# SDCARD.net
KiCad netlist of a schematic drawn in Altium Designer
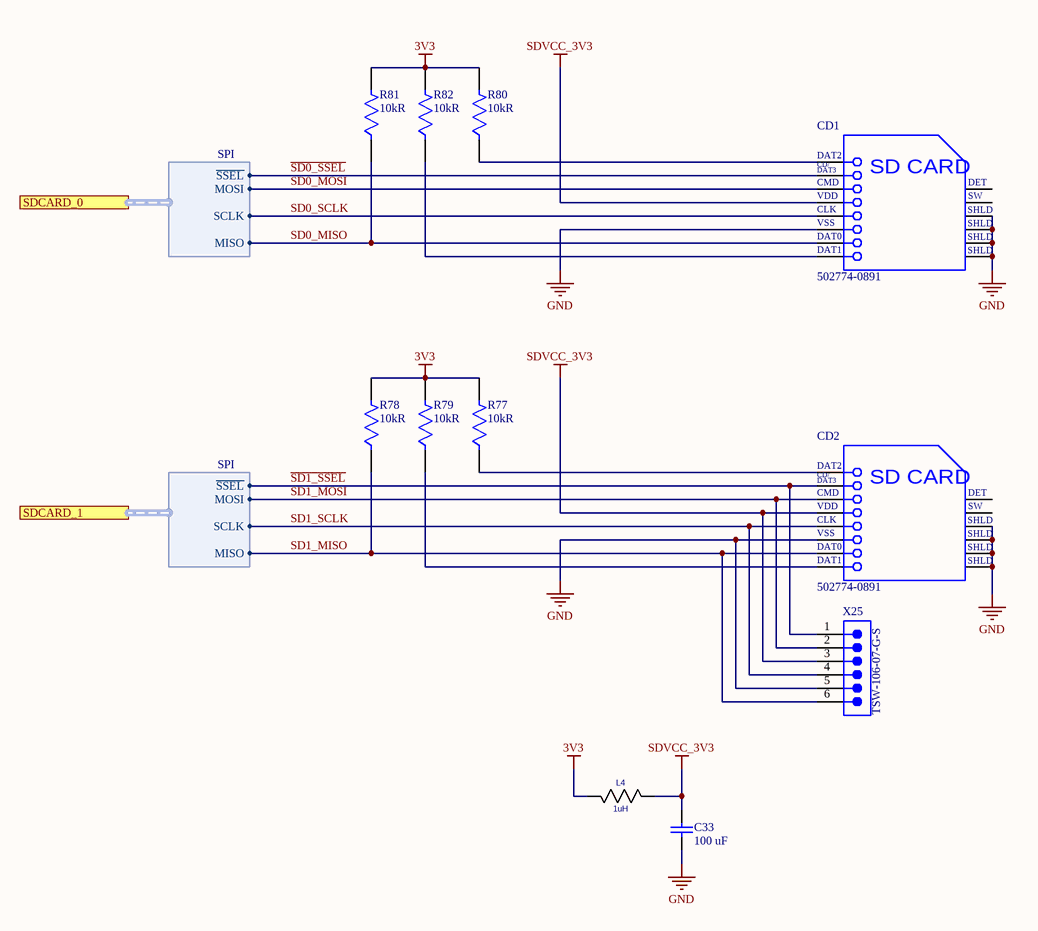
[diagram p0: SDCARD.SchDoc]

(export (version "E")
  (design (tool "Eeschema 10.0.6"))
  (components
    (comp (ref "C33")
      (value "GRM31CR60J107ME39L")
      (footprint "CAPC3216X190X55ML30T25")
      (description "Chip Capacitor, 100 uF, +/- 20%, 6.3 V, -55 to 85 degC, 1206 (3216 Metric), RoHS, Tape and Reel")
      (fields (field (name "CAPACITANCE") "100 uF") (field (name "MANUFACTURER") "Murata"))
      (libsource (lib "SchLib") (part "CMP-1662-00011-2"))
    )
    (comp (ref "CD1")
      (value "502774-0891")
      (footprint "MOLX-502774-0891_V")
      (description "Micro SD Memory Card Connector, 0.5 A, 10 V (DC), -25 to 85 degC, 8-Pin SMT, RoHS, Tape and Reel")
      (fields (field (name "MANUFACTURER") "Molex") (field (name "MANUFACTURER PART NUMBER") "5027740891"))
      (libsource (lib "SchLib") (part "CMP-2000-05248-1"))
    )
    (comp (ref "CD2")
      (value "502774-0891")
      (footprint "MOLX-502774-0891_V")
      (description "Micro SD Memory Card Connector, 0.5 A, 10 V (DC), -25 to 85 degC, 8-Pin SMT, RoHS, Tape and Reel")
      (fields (field (name "MANUFACTURER") "Molex") (field (name "MANUFACTURER PART NUMBER") "5027740891"))
      (libsource (lib "SchLib") (part "CMP-2000-05248-1"))
    )
    (comp (ref "L4")
      (value "1uH")
      (footprint "L-CHIP")
      (description "L-CHIP")
      (libsource (lib "SchLib") (part "L-CHIP"))
    )
    (comp (ref "R77")
      (value "CR0805-JW-103ELF")
      (footprint "FP-CR0805-IPC_A")
      (description "Thick Film Chip Resistors 0805 10kΩ 0.125W 5% 200ppm/°C")
      (fields (field (name "RESISTANCE") "10kR") (field (name "MANUFACTURER") "Bourns"))
      (libsource (lib "SchLib") (part "CMP-07231-003873-1"))
    )
    (comp (ref "R78")
      (value "CR0805-JW-103ELF")
      (footprint "FP-CR0805-IPC_A")
      (description "Thick Film Chip Resistors 0805 10kΩ 0.125W 5% 200ppm/°C")
      (fields (field (name "RESISTANCE") "10kR") (field (name "MANUFACTURER") "Bourns"))
      (libsource (lib "SchLib") (part "CMP-07231-003873-1"))
    )
    (comp (ref "R79")
      (value "CR0805-JW-103ELF")
      (footprint "FP-CR0805-IPC_A")
      (description "Thick Film Chip Resistors 0805 10kΩ 0.125W 5% 200ppm/°C")
      (fields (field (name "RESISTANCE") "10kR") (field (name "MANUFACTURER") "Bourns"))
      (libsource (lib "SchLib") (part "CMP-07231-003873-1"))
    )
    (comp (ref "R80")
      (value "CR0805-JW-103ELF")
      (footprint "FP-CR0805-IPC_A")
      (description "Thick Film Chip Resistors 0805 10kΩ 0.125W 5% 200ppm/°C")
      (fields (field (name "RESISTANCE") "10kR") (field (name "MANUFACTURER") "Bourns"))
      (libsource (lib "SchLib") (part "CMP-07231-003873-1"))
    )
    (comp (ref "R81")
      (value "CR0805-JW-103ELF")
      (footprint "FP-CR0805-IPC_A")
      (description "Thick Film Chip Resistors 0805 10kΩ 0.125W 5% 200ppm/°C")
      (fields (field (name "RESISTANCE") "10kR") (field (name "MANUFACTURER") "Bourns"))
      (libsource (lib "SchLib") (part "CMP-07231-003873-1"))
    )
    (comp (ref "R82")
      (value "CR0805-JW-103ELF")
      (footprint "FP-CR0805-IPC_A")
      (description "Thick Film Chip Resistors 0805 10kΩ 0.125W 5% 200ppm/°C")
      (fields (field (name "RESISTANCE") "10kR") (field (name "MANUFACTURER") "Bourns"))
      (libsource (lib "SchLib") (part "CMP-07231-003873-1"))
    )
    (comp (ref "X25")
      (value "TSW-106-07-G-S")
      (footprint "SMTC-TSW-106-07-X-S")
      (description "0.025\" SQ Post Header, Through-hole, Vertical, -55 to 125 degC, 2.54 mm Pitch, 6-Pin, Male, RoHS")
      (fields (field (name "MANUFACTURER") "Samtec"))
      (libsource (lib "SchLib") (part "CMP-1024-00383-1"))
    )
  )
  (nets
    (net (code "2") (name "/SD0_MISO") (class "Default")
      (node (ref "CD1") (pin "7") (pinfunction "DAT0_7") (pintype "passive"))
      (node (ref "R81") (pin "1") (pinfunction "1_1") (pintype "passive"))
    )
    (net (code "3") (name "/SD0_MOSI") (class "Default")
      (node (ref "CD1") (pin "3") (pinfunction "CMD_3") (pintype "passive"))
    )
    (net (code "4") (name "/SD0_SCLK") (class "Default")
      (node (ref "CD1") (pin "5") (pinfunction "CLK_5") (pintype "passive"))
    )
    (net (code "5") (name "/SD1_MISO") (class "Default")
      (node (ref "CD2") (pin "7") (pinfunction "DAT0_7") (pintype "passive"))
      (node (ref "R78") (pin "1") (pinfunction "1_1") (pintype "passive"))
      (node (ref "X25") (pin "6") (pinfunction "6_6") (pintype "passive"))
    )
    (net (code "6") (name "/SD1_MOSI") (class "Default")
      (node (ref "CD2") (pin "3") (pinfunction "CMD_3") (pintype "passive"))
      (node (ref "X25") (pin "2") (pinfunction "2_2") (pintype "passive"))
    )
    (net (code "7") (name "/SD1_SCLK") (class "Default")
      (node (ref "CD2") (pin "5") (pinfunction "CLK_5") (pintype "passive"))
      (node (ref "X25") (pin "4") (pinfunction "4_4") (pintype "passive"))
    )
    (net (code "9") (name "/~{SD0_SSEL}") (class "Default")
      (node (ref "CD1") (pin "2") (pinfunction "CD/DAT3_2") (pintype "passive"))
    )
    (net (code "10") (name "/~{SD1_SSEL}") (class "Default")
      (node (ref "CD2") (pin "2") (pinfunction "CD/DAT3_2") (pintype "passive"))
      (node (ref "X25") (pin "1") (pinfunction "1_1") (pintype "passive"))
    )
    (net (code "11") (name "3V3") (class "Default")
      (node (ref "L4") (pin "2") (pintype "passive"))
      (node (ref "R77") (pin "2") (pinfunction "2_2") (pintype "passive"))
      (node (ref "R78") (pin "2") (pinfunction "2_2") (pintype "passive"))
      (node (ref "R79") (pin "2") (pinfunction "2_2") (pintype "passive"))
      (node (ref "R80") (pin "2") (pinfunction "2_2") (pintype "passive"))
      (node (ref "R81") (pin "2") (pinfunction "2_2") (pintype "passive"))
      (node (ref "R82") (pin "2") (pinfunction "2_2") (pintype "passive"))
    )
    (net (code "12") (name "GND") (class "Default")
      (node (ref "C33") (pin "1") (pinfunction "1_1") (pintype "passive"))
      (node (ref "CD1") (pin "11") (pinfunction "SHLD_11") (pintype "passive"))
      (node (ref "CD1") (pin "12") (pinfunction "SHLD_12") (pintype "passive"))
      (node (ref "CD1") (pin "13") (pinfunction "SHLD_13") (pintype "passive"))
      (node (ref "CD1") (pin "14") (pinfunction "SHLD_14") (pintype "passive"))
      (node (ref "CD1") (pin "6") (pinfunction "VSS_6") (pintype "passive"))
      (node (ref "CD2") (pin "11") (pinfunction "SHLD_11") (pintype "passive"))
      (node (ref "CD2") (pin "12") (pinfunction "SHLD_12") (pintype "passive"))
      (node (ref "CD2") (pin "13") (pinfunction "SHLD_13") (pintype "passive"))
      (node (ref "CD2") (pin "14") (pinfunction "SHLD_14") (pintype "passive"))
      (node (ref "CD2") (pin "6") (pinfunction "VSS_6") (pintype "passive"))
      (node (ref "X25") (pin "5") (pinfunction "5_5") (pintype "passive"))
    )
    (net (code "13") (name "Net-(CD1-DAT1)") (class "Default")
      (node (ref "CD1") (pin "8") (pinfunction "DAT1_8") (pintype "passive"))
      (node (ref "R82") (pin "1") (pinfunction "1_1") (pintype "passive"))
    )
    (net (code "14") (name "Net-(CD1-DAT2)") (class "Default")
      (node (ref "CD1") (pin "1") (pinfunction "DAT2_1") (pintype "passive"))
      (node (ref "R80") (pin "1") (pinfunction "1_1") (pintype "passive"))
    )
    (net (code "15") (name "Net-(CD2-DAT1)") (class "Default")
      (node (ref "CD2") (pin "8") (pinfunction "DAT1_8") (pintype "passive"))
      (node (ref "R79") (pin "1") (pinfunction "1_1") (pintype "passive"))
    )
    (net (code "16") (name "Net-(CD2-DAT2)") (class "Default")
      (node (ref "CD2") (pin "1") (pinfunction "DAT2_1") (pintype "passive"))
      (node (ref "R77") (pin "1") (pinfunction "1_1") (pintype "passive"))
    )
    (net (code "17") (name "SDVCC_3V3") (class "Default")
      (node (ref "C33") (pin "2") (pinfunction "2_2") (pintype "passive"))
      (node (ref "CD1") (pin "4") (pinfunction "VDD_4") (pintype "passive"))
      (node (ref "CD2") (pin "4") (pinfunction "VDD_4") (pintype "passive"))
      (node (ref "L4") (pin "1") (pintype "passive"))
      (node (ref "X25") (pin "3") (pinfunction "3_3") (pintype "passive"))
    )
    (net (code "18") (name "unconnected-(CD1-DETECT-Pad9)") (class "Default")
      (node (ref "CD1") (pin "9") (pinfunction "DETECT_9") (pintype "passive"))
    )
    (net (code "19") (name "unconnected-(CD1-SWITCH-Pad10)") (class "Default")
      (node (ref "CD1") (pin "10") (pinfunction "SWITCH_10") (pintype "passive"))
    )
    (net (code "20") (name "unconnected-(CD2-DETECT-Pad9)") (class "Default")
      (node (ref "CD2") (pin "9") (pinfunction "DETECT_9") (pintype "passive"))
    )
    (net (code "21") (name "unconnected-(CD2-SWITCH-Pad10)") (class "Default")
      (node (ref "CD2") (pin "10") (pinfunction "SWITCH_10") (pintype "passive"))
    )
  )
)
